# Digital_Input.net
KiCad netlist of a schematic drawn in Altium Designer
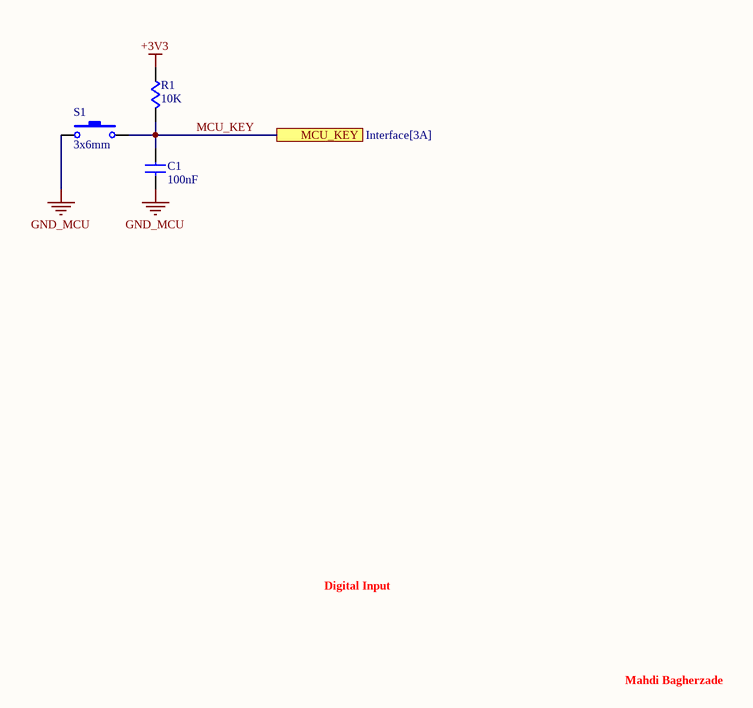
[diagram p0: Digital Input.SchDoc]

(export (version "E")
  (design (tool "Eeschema 10.0.6"))
  (components
    (comp (ref "C1")
      (value "100nF")
      (footprint "C-0805")
      (description "CAPACITOR")
      (fields
        (field (name "VOLTAGE") "50V")
        (field (name "TOLERANCE") "X7R")
        (field (name "PUBLISHER") "Mahdi Bagherzadeh")
      )
      (libsource (lib "Mahdi-Bagherzadeh") (part "CAP-CER"))
    )
    (comp (ref "R1")
      (value "10K")
      (footprint "R-0805")
      (description "RESISTOR")
      (fields
        (field (name "TOLERANCE") "5%")
        (field (name "POWER") "1/8W")
        (field (name "PUBLISHER") "Mahdi Bagherzadeh")
      )
      (libsource (lib "Mahdi-Bagherzadeh") (part "RES"))
    )
    (comp (ref "S1")
      (value "Push Button 3x6mm-2Pin-SMD")
      (footprint "SW-SMD-2pin-3x6")
      (description "SWITCH")
      (fields (field (name "SIZE") "3x6mm") (field (name "PUBLISHER") "Mahdi Bagherzadeh"))
      (libsource (lib "Mahdi-Bagherzadeh") (part "PUSH BUTTON"))
    )
  )
  (nets
    (net (code "1") (name "+3V3") (class "Default")
      (node (ref "R1") (pin "1") (pinfunction "1_1") (pintype "passive"))
    )
    (net (code "2") (name "/MCU_KEY") (class "Default")
      (node (ref "C1") (pin "1") (pinfunction "1_1") (pintype "passive"))
      (node (ref "R1") (pin "2") (pinfunction "2_2") (pintype "passive"))
      (node (ref "S1") (pin "2") (pinfunction "2_2") (pintype "passive"))
    )
    (net (code "3") (name "GND_MCU") (class "Default")
      (node (ref "C1") (pin "2") (pinfunction "2_2") (pintype "passive"))
      (node (ref "S1") (pin "1") (pinfunction "1_1") (pintype "passive"))
    )
  )
)
